# SH4_-_LEVEL_SHIFTERS.net
KiCad netlist of a schematic drawn in Altium Designer
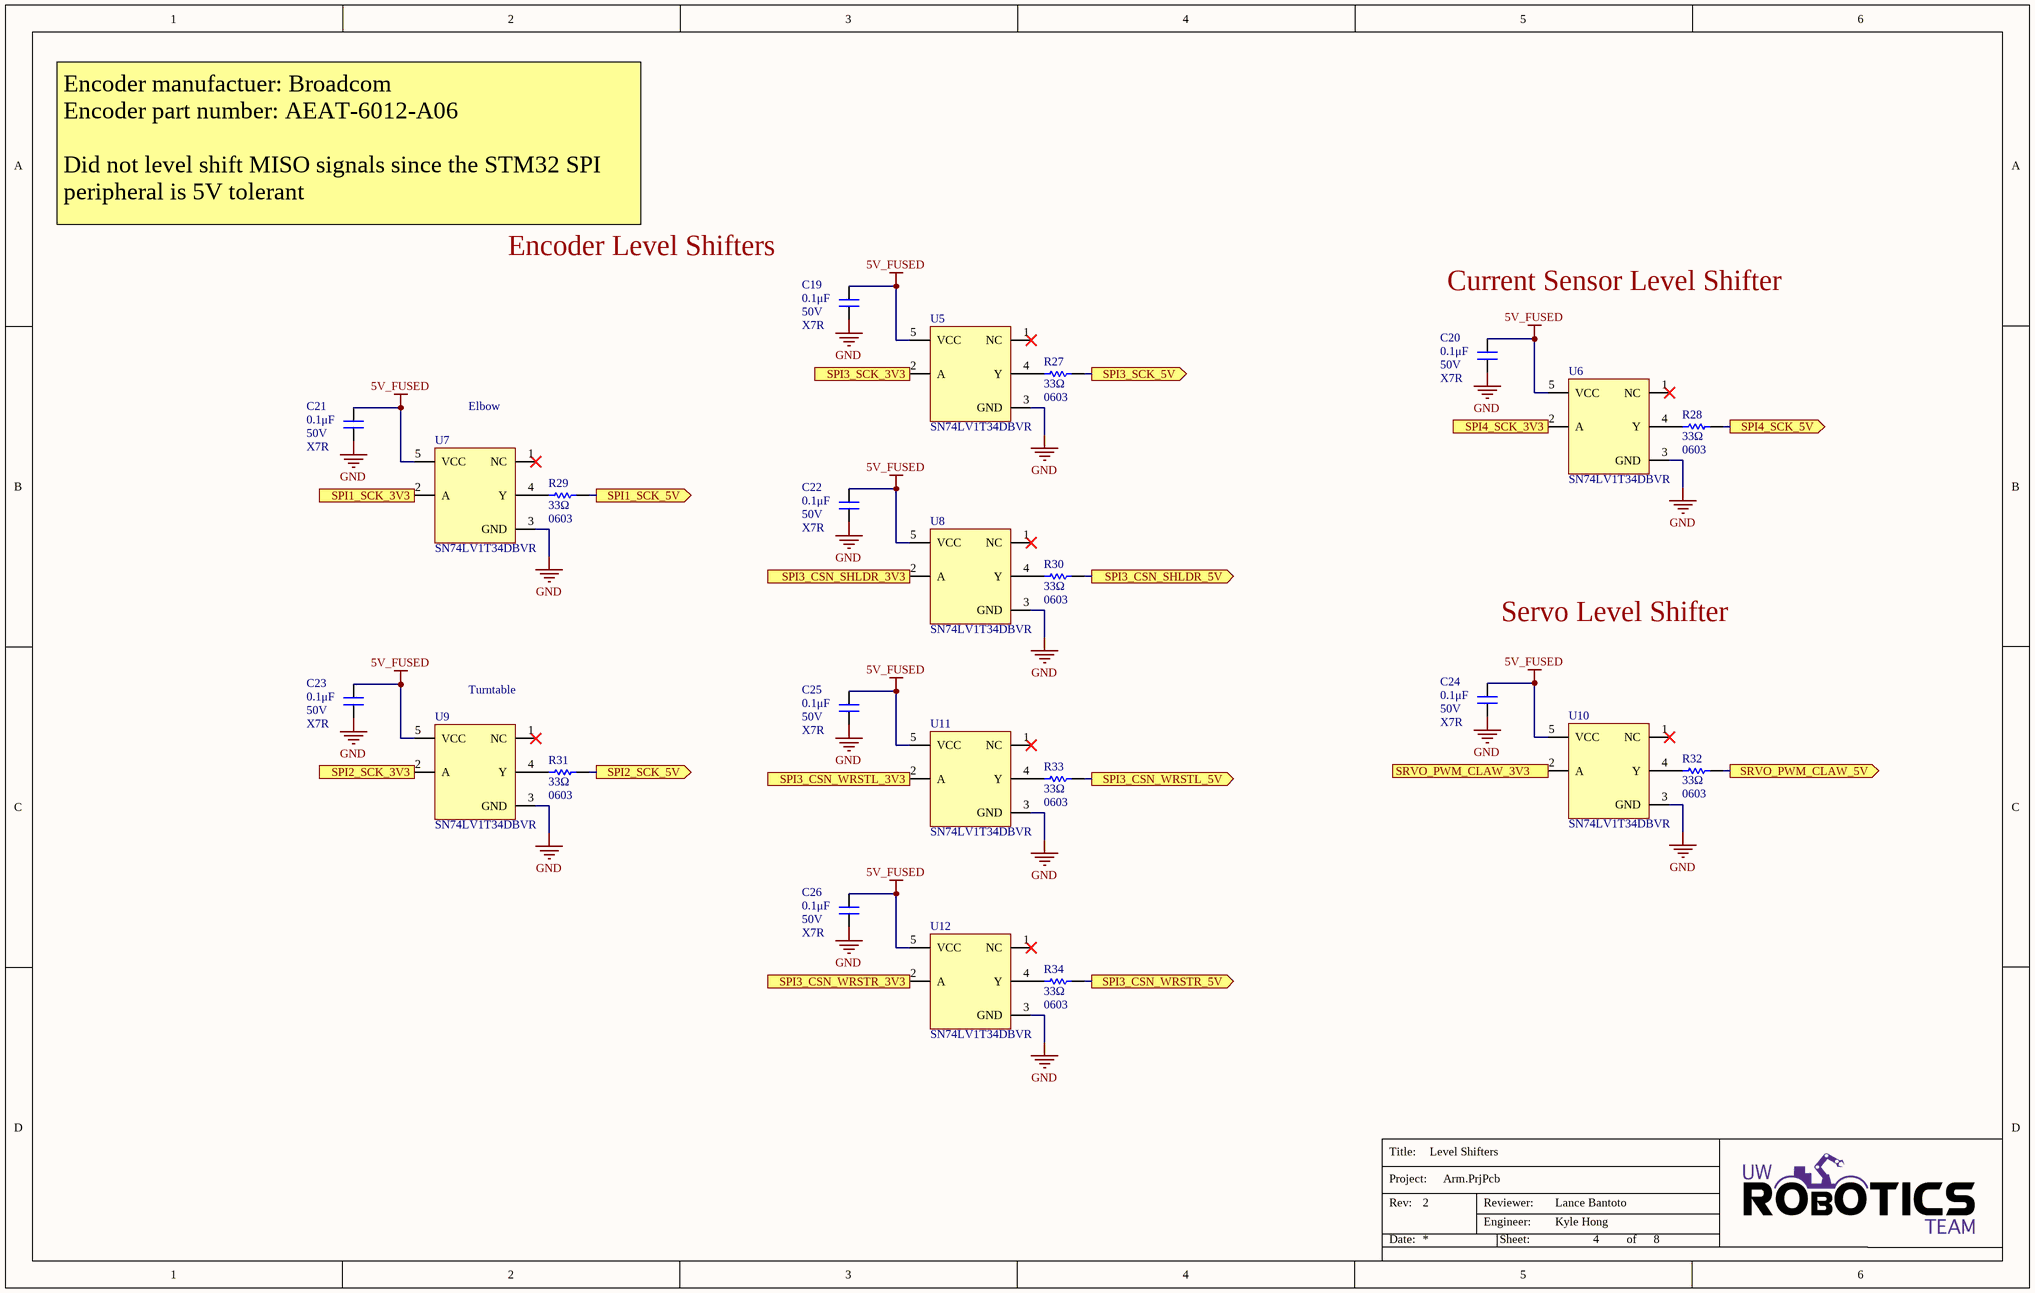
[diagram p0: SH4 - LEVEL SHIFTERS.SchDoc]

(export (version "E")
  (design (tool "Eeschema 10.0.6"))
  (components
    (comp (ref "C19")
      (value "0.1μF")
      (footprint "CAP0603")
      (description "CAP CER 0.1UF 50V X7R 0603")
      (fields
        (field (name "DIELECTRIC") "X7R")
        (field (name "VOLTAGE RATING") "50V")
        (field (name "Comment") "CAP_0.1uF_50V_0603")
      )
      (libsource (lib "UWRT_Schematic_Library_2020") (part "CAP_0.1uF_50V_0603"))
    )
    (comp (ref "C20")
      (value "0.1μF")
      (footprint "CAP0603")
      (description "CAP CER 0.1UF 50V X7R 0603")
      (fields
        (field (name "DIELECTRIC") "X7R")
        (field (name "VOLTAGE RATING") "50V")
        (field (name "Comment") "CAP_0.1uF_50V_0603")
      )
      (libsource (lib "UWRT_Schematic_Library_2020") (part "CAP_0.1uF_50V_0603"))
    )
    (comp (ref "C21")
      (value "0.1μF")
      (footprint "CAP0603")
      (description "CAP CER 0.1UF 50V X7R 0603")
      (fields
        (field (name "DIELECTRIC") "X7R")
        (field (name "VOLTAGE RATING") "50V")
        (field (name "Comment") "CAP_0.1uF_50V_0603")
      )
      (libsource (lib "UWRT_Schematic_Library_2020") (part "CAP_0.1uF_50V_0603"))
    )
    (comp (ref "C22")
      (value "0.1μF")
      (footprint "CAP0603")
      (description "CAP CER 0.1UF 50V X7R 0603")
      (fields
        (field (name "DIELECTRIC") "X7R")
        (field (name "VOLTAGE RATING") "50V")
        (field (name "Comment") "CAP_0.1uF_50V_0603")
      )
      (libsource (lib "UWRT_Schematic_Library_2020") (part "CAP_0.1uF_50V_0603"))
    )
    (comp (ref "C23")
      (value "0.1μF")
      (footprint "CAP0603")
      (description "CAP CER 0.1UF 50V X7R 0603")
      (fields
        (field (name "DIELECTRIC") "X7R")
        (field (name "VOLTAGE RATING") "50V")
        (field (name "Comment") "CAP_0.1uF_50V_0603")
      )
      (libsource (lib "UWRT_Schematic_Library_2020") (part "CAP_0.1uF_50V_0603"))
    )
    (comp (ref "C24")
      (value "0.1μF")
      (footprint "CAP0603")
      (description "CAP CER 0.1UF 50V X7R 0603")
      (fields
        (field (name "DIELECTRIC") "X7R")
        (field (name "VOLTAGE RATING") "50V")
        (field (name "Comment") "CAP_0.1uF_50V_0603")
      )
      (libsource (lib "UWRT_Schematic_Library_2020") (part "CAP_0.1uF_50V_0603"))
    )
    (comp (ref "C25")
      (value "0.1μF")
      (footprint "CAP0603")
      (description "CAP CER 0.1UF 50V X7R 0603")
      (fields
        (field (name "DIELECTRIC") "X7R")
        (field (name "VOLTAGE RATING") "50V")
        (field (name "Comment") "CAP_0.1uF_50V_0603")
      )
      (libsource (lib "UWRT_Schematic_Library_2020") (part "CAP_0.1uF_50V_0603"))
    )
    (comp (ref "C26")
      (value "0.1μF")
      (footprint "CAP0603")
      (description "CAP CER 0.1UF 50V X7R 0603")
      (fields
        (field (name "DIELECTRIC") "X7R")
        (field (name "VOLTAGE RATING") "50V")
        (field (name "Comment") "CAP_0.1uF_50V_0603")
      )
      (libsource (lib "UWRT_Schematic_Library_2020") (part "CAP_0.1uF_50V_0603"))
    )
    (comp (ref "R27")
      (value "RES_33Ω_0603_1%")
      (footprint "RESC0603")
      (description "RES 33 OHM 1% 1/10W 0603")
      (fields
        (field (name "TOLERANCE") "1%")
        (field (name "RESISTANCE") "33Ω")
        (field (name "PACKAGE/FOOTPRINT") "0603")
      )
      (libsource (lib "UWRT_Schematic_Library_2020") (part "RES_33Ω_0603_1%"))
    )
    (comp (ref "R28")
      (value "RES_33Ω_0603_1%")
      (footprint "RESC0603")
      (description "RES 33 OHM 1% 1/10W 0603")
      (fields
        (field (name "TOLERANCE") "1%")
        (field (name "RESISTANCE") "33Ω")
        (field (name "PACKAGE/FOOTPRINT") "0603")
      )
      (libsource (lib "UWRT_Schematic_Library_2020") (part "RES_33Ω_0603_1%"))
    )
    (comp (ref "R29")
      (value "RES_33Ω_0603_1%")
      (footprint "RESC0603")
      (description "RES 33 OHM 1% 1/10W 0603")
      (fields
        (field (name "TOLERANCE") "1%")
        (field (name "RESISTANCE") "33Ω")
        (field (name "PACKAGE/FOOTPRINT") "0603")
      )
      (libsource (lib "UWRT_Schematic_Library_2020") (part "RES_33Ω_0603_1%"))
    )
    (comp (ref "R30")
      (value "RES_33Ω_0603_1%")
      (footprint "RESC0603")
      (description "RES 33 OHM 1% 1/10W 0603")
      (fields
        (field (name "TOLERANCE") "1%")
        (field (name "RESISTANCE") "33Ω")
        (field (name "PACKAGE/FOOTPRINT") "0603")
      )
      (libsource (lib "UWRT_Schematic_Library_2020") (part "RES_33Ω_0603_1%"))
    )
    (comp (ref "R31")
      (value "RES_33Ω_0603_1%")
      (footprint "RESC0603")
      (description "RES 33 OHM 1% 1/10W 0603")
      (fields
        (field (name "TOLERANCE") "1%")
        (field (name "RESISTANCE") "33Ω")
        (field (name "PACKAGE/FOOTPRINT") "0603")
      )
      (libsource (lib "UWRT_Schematic_Library_2020") (part "RES_33Ω_0603_1%"))
    )
    (comp (ref "R32")
      (value "RES_33Ω_0603_1%")
      (footprint "RESC0603")
      (description "RES 33 OHM 1% 1/10W 0603")
      (fields
        (field (name "TOLERANCE") "1%")
        (field (name "RESISTANCE") "33Ω")
        (field (name "PACKAGE/FOOTPRINT") "0603")
      )
      (libsource (lib "UWRT_Schematic_Library_2020") (part "RES_33Ω_0603_1%"))
    )
    (comp (ref "R33")
      (value "RES_33Ω_0603_1%")
      (footprint "RESC0603")
      (description "RES 33 OHM 1% 1/10W 0603")
      (fields
        (field (name "TOLERANCE") "1%")
        (field (name "RESISTANCE") "33Ω")
        (field (name "PACKAGE/FOOTPRINT") "0603")
      )
      (libsource (lib "UWRT_Schematic_Library_2020") (part "RES_33Ω_0603_1%"))
    )
    (comp (ref "R34")
      (value "RES_33Ω_0603_1%")
      (footprint "RESC0603")
      (description "RES 33 OHM 1% 1/10W 0603")
      (fields
        (field (name "TOLERANCE") "1%")
        (field (name "RESISTANCE") "33Ω")
        (field (name "PACKAGE/FOOTPRINT") "0603")
      )
      (libsource (lib "UWRT_Schematic_Library_2020") (part "RES_33Ω_0603_1%"))
    )
    (comp (ref "U5")
      (value "SN74LV1T34")
      (footprint "SN74LV1T34DBVR")
      (description "IC BUF NON-INVERT 5.5V SOT23-5")
      (fields
        (field (name "MANUFACTURER PART NUMBER 1") "SN74LV1T34DBVR")
        (field (name "LCSC PART #") "C100024")
      )
      (libsource (lib "UWRT_Schematic_Library_2020") (part "SN74LV1T34"))
    )
    (comp (ref "U6")
      (value "SN74LV1T34")
      (footprint "SN74LV1T34DBVR")
      (description "IC BUF NON-INVERT 5.5V SOT23-5")
      (fields
        (field (name "MANUFACTURER PART NUMBER 1") "SN74LV1T34DBVR")
        (field (name "LCSC PART #") "C100024")
      )
      (libsource (lib "UWRT_Schematic_Library_2020") (part "SN74LV1T34"))
    )
    (comp (ref "U7")
      (value "SN74LV1T34")
      (footprint "SN74LV1T34DBVR")
      (description "IC BUF NON-INVERT 5.5V SOT23-5")
      (fields
        (field (name "MANUFACTURER PART NUMBER 1") "SN74LV1T34DBVR")
        (field (name "LCSC PART #") "C100024")
      )
      (libsource (lib "UWRT_Schematic_Library_2020") (part "SN74LV1T34"))
    )
    (comp (ref "U8")
      (value "SN74LV1T34")
      (footprint "SN74LV1T34DBVR")
      (description "IC BUF NON-INVERT 5.5V SOT23-5")
      (fields
        (field (name "MANUFACTURER PART NUMBER 1") "SN74LV1T34DBVR")
        (field (name "LCSC PART #") "C100024")
      )
      (libsource (lib "UWRT_Schematic_Library_2020") (part "SN74LV1T34"))
    )
    (comp (ref "U9")
      (value "SN74LV1T34")
      (footprint "SN74LV1T34DBVR")
      (description "IC BUF NON-INVERT 5.5V SOT23-5")
      (fields
        (field (name "MANUFACTURER PART NUMBER 1") "SN74LV1T34DBVR")
        (field (name "LCSC PART #") "C100024")
      )
      (libsource (lib "UWRT_Schematic_Library_2020") (part "SN74LV1T34"))
    )
    (comp (ref "U10")
      (value "SN74LV1T34")
      (footprint "SN74LV1T34DBVR")
      (description "IC BUF NON-INVERT 5.5V SOT23-5")
      (fields
        (field (name "MANUFACTURER PART NUMBER 1") "SN74LV1T34DBVR")
        (field (name "LCSC PART #") "C100024")
      )
      (libsource (lib "UWRT_Schematic_Library_2020") (part "SN74LV1T34"))
    )
    (comp (ref "U11")
      (value "SN74LV1T34")
      (footprint "SN74LV1T34DBVR")
      (description "IC BUF NON-INVERT 5.5V SOT23-5")
      (fields
        (field (name "MANUFACTURER PART NUMBER 1") "SN74LV1T34DBVR")
        (field (name "LCSC PART #") "C100024")
      )
      (libsource (lib "UWRT_Schematic_Library_2020") (part "SN74LV1T34"))
    )
    (comp (ref "U12")
      (value "SN74LV1T34")
      (footprint "SN74LV1T34DBVR")
      (description "IC BUF NON-INVERT 5.5V SOT23-5")
      (fields
        (field (name "MANUFACTURER PART NUMBER 1") "SN74LV1T34DBVR")
        (field (name "LCSC PART #") "C100024")
      )
      (libsource (lib "UWRT_Schematic_Library_2020") (part "SN74LV1T34"))
    )
  )
  (nets
    (net (code "1") (name "/SPI1_SCK_3V3") (class "Default")
      (node (ref "U7") (pin "2") (pinfunction "A_2") (pintype "passive"))
    )
    (net (code "2") (name "/SPI1_SCK_5V") (class "Default")
      (node (ref "R29") (pin "2") (pinfunction "2_2") (pintype "passive"))
    )
    (net (code "3") (name "/SPI2_SCK_3V3") (class "Default")
      (node (ref "U9") (pin "2") (pinfunction "A_2") (pintype "passive"))
    )
    (net (code "4") (name "/SPI2_SCK_5V") (class "Default")
      (node (ref "R31") (pin "2") (pinfunction "2_2") (pintype "passive"))
    )
    (net (code "5") (name "/SPI3_CSN_SHLDR_3V3") (class "Default")
      (node (ref "U8") (pin "2") (pinfunction "A_2") (pintype "passive"))
    )
    (net (code "6") (name "/SPI3_CSN_SHLDR_5V") (class "Default")
      (node (ref "R30") (pin "2") (pinfunction "2_2") (pintype "passive"))
    )
    (net (code "7") (name "/SPI3_CSN_WRSTL_3V3") (class "Default")
      (node (ref "U11") (pin "2") (pinfunction "A_2") (pintype "passive"))
    )
    (net (code "8") (name "/SPI3_CSN_WRSTL_5V") (class "Default")
      (node (ref "R33") (pin "2") (pinfunction "2_2") (pintype "passive"))
    )
    (net (code "9") (name "/SPI3_CSN_WRSTR_3V3") (class "Default")
      (node (ref "U12") (pin "2") (pinfunction "A_2") (pintype "passive"))
    )
    (net (code "10") (name "/SPI3_CSN_WRSTR_5V") (class "Default")
      (node (ref "R34") (pin "2") (pinfunction "2_2") (pintype "passive"))
    )
    (net (code "11") (name "/SPI3_SCK_3V3") (class "Default")
      (node (ref "U5") (pin "2") (pinfunction "A_2") (pintype "passive"))
    )
    (net (code "12") (name "/SPI3_SCK_5V") (class "Default")
      (node (ref "R27") (pin "2") (pinfunction "2_2") (pintype "passive"))
    )
    (net (code "13") (name "/SPI4_SCK_3V3") (class "Default")
      (node (ref "U6") (pin "2") (pinfunction "A_2") (pintype "passive"))
    )
    (net (code "14") (name "/SPI4_SCK_5V") (class "Default")
      (node (ref "R28") (pin "2") (pinfunction "2_2") (pintype "passive"))
    )
    (net (code "15") (name "/SRVO_PWM_CLAW_3V3") (class "Default")
      (node (ref "U10") (pin "2") (pinfunction "A_2") (pintype "passive"))
    )
    (net (code "16") (name "/SRVO_PWM_CLAW_5V") (class "Default")
      (node (ref "R32") (pin "2") (pinfunction "2_2") (pintype "passive"))
    )
    (net (code "17") (name "5V_FUSED") (class "Default")
      (node (ref "C19") (pin "2") (pinfunction "2_2") (pintype "passive"))
      (node (ref "C20") (pin "2") (pinfunction "2_2") (pintype "passive"))
      (node (ref "C21") (pin "2") (pinfunction "2_2") (pintype "passive"))
      (node (ref "C22") (pin "2") (pinfunction "2_2") (pintype "passive"))
      (node (ref "C23") (pin "2") (pinfunction "2_2") (pintype "passive"))
      (node (ref "C24") (pin "2") (pinfunction "2_2") (pintype "passive"))
      (node (ref "C25") (pin "2") (pinfunction "2_2") (pintype "passive"))
      (node (ref "C26") (pin "2") (pinfunction "2_2") (pintype "passive"))
      (node (ref "U10") (pin "5") (pinfunction "VCC_5") (pintype "passive"))
      (node (ref "U11") (pin "5") (pinfunction "VCC_5") (pintype "passive"))
      (node (ref "U12") (pin "5") (pinfunction "VCC_5") (pintype "passive"))
      (node (ref "U5") (pin "5") (pinfunction "VCC_5") (pintype "passive"))
      (node (ref "U6") (pin "5") (pinfunction "VCC_5") (pintype "passive"))
      (node (ref "U7") (pin "5") (pinfunction "VCC_5") (pintype "passive"))
      (node (ref "U8") (pin "5") (pinfunction "VCC_5") (pintype "passive"))
      (node (ref "U9") (pin "5") (pinfunction "VCC_5") (pintype "passive"))
    )
    (net (code "18") (name "GND") (class "Default")
      (node (ref "C19") (pin "1") (pinfunction "1_1") (pintype "passive"))
      (node (ref "C20") (pin "1") (pinfunction "1_1") (pintype "passive"))
      (node (ref "C21") (pin "1") (pinfunction "1_1") (pintype "passive"))
      (node (ref "C22") (pin "1") (pinfunction "1_1") (pintype "passive"))
      (node (ref "C23") (pin "1") (pinfunction "1_1") (pintype "passive"))
      (node (ref "C24") (pin "1") (pinfunction "1_1") (pintype "passive"))
      (node (ref "C25") (pin "1") (pinfunction "1_1") (pintype "passive"))
      (node (ref "C26") (pin "1") (pinfunction "1_1") (pintype "passive"))
      (node (ref "U10") (pin "3") (pinfunction "GND_3") (pintype "passive"))
      (node (ref "U11") (pin "3") (pinfunction "GND_3") (pintype "passive"))
      (node (ref "U12") (pin "3") (pinfunction "GND_3") (pintype "passive"))
      (node (ref "U5") (pin "3") (pinfunction "GND_3") (pintype "passive"))
      (node (ref "U6") (pin "3") (pinfunction "GND_3") (pintype "passive"))
      (node (ref "U7") (pin "3") (pinfunction "GND_3") (pintype "passive"))
      (node (ref "U8") (pin "3") (pinfunction "GND_3") (pintype "passive"))
      (node (ref "U9") (pin "3") (pinfunction "GND_3") (pintype "passive"))
    )
    (net (code "19") (name "Net-(U5-Y)") (class "Default")
      (node (ref "R27") (pin "1") (pinfunction "1_1") (pintype "passive"))
      (node (ref "U5") (pin "4") (pinfunction "Y_4") (pintype "passive"))
    )
    (net (code "20") (name "Net-(U6-Y)") (class "Default")
      (node (ref "R28") (pin "1") (pinfunction "1_1") (pintype "passive"))
      (node (ref "U6") (pin "4") (pinfunction "Y_4") (pintype "passive"))
    )
    (net (code "21") (name "Net-(U7-Y)") (class "Default")
      (node (ref "R29") (pin "1") (pinfunction "1_1") (pintype "passive"))
      (node (ref "U7") (pin "4") (pinfunction "Y_4") (pintype "passive"))
    )
    (net (code "22") (name "Net-(U8-Y)") (class "Default")
      (node (ref "R30") (pin "1") (pinfunction "1_1") (pintype "passive"))
      (node (ref "U8") (pin "4") (pinfunction "Y_4") (pintype "passive"))
    )
    (net (code "23") (name "Net-(U9-Y)") (class "Default")
      (node (ref "R31") (pin "1") (pinfunction "1_1") (pintype "passive"))
      (node (ref "U9") (pin "4") (pinfunction "Y_4") (pintype "passive"))
    )
    (net (code "24") (name "Net-(U10-Y)") (class "Default")
      (node (ref "R32") (pin "1") (pinfunction "1_1") (pintype "passive"))
      (node (ref "U10") (pin "4") (pinfunction "Y_4") (pintype "passive"))
    )
    (net (code "25") (name "Net-(U11-Y)") (class "Default")
      (node (ref "R33") (pin "1") (pinfunction "1_1") (pintype "passive"))
      (node (ref "U11") (pin "4") (pinfunction "Y_4") (pintype "passive"))
    )
    (net (code "26") (name "Net-(U12-Y)") (class "Default")
      (node (ref "R34") (pin "1") (pinfunction "1_1") (pintype "passive"))
      (node (ref "U12") (pin "4") (pinfunction "Y_4") (pintype "passive"))
    )
    (net (code "27") (name "unconnected-(U5-NC-Pad1)") (class "Default")
      (node (ref "U5") (pin "1") (pinfunction "NC_1") (pintype "passive+no_connect"))
    )
    (net (code "28") (name "unconnected-(U6-NC-Pad1)") (class "Default")
      (node (ref "U6") (pin "1") (pinfunction "NC_1") (pintype "passive+no_connect"))
    )
    (net (code "29") (name "unconnected-(U7-NC-Pad1)") (class "Default")
      (node (ref "U7") (pin "1") (pinfunction "NC_1") (pintype "passive+no_connect"))
    )
    (net (code "30") (name "unconnected-(U8-NC-Pad1)") (class "Default")
      (node (ref "U8") (pin "1") (pinfunction "NC_1") (pintype "passive+no_connect"))
    )
    (net (code "31") (name "unconnected-(U9-NC-Pad1)") (class "Default")
      (node (ref "U9") (pin "1") (pinfunction "NC_1") (pintype "passive+no_connect"))
    )
    (net (code "32") (name "unconnected-(U10-NC-Pad1)") (class "Default")
      (node (ref "U10") (pin "1") (pinfunction "NC_1") (pintype "passive+no_connect"))
    )
    (net (code "33") (name "unconnected-(U11-NC-Pad1)") (class "Default")
      (node (ref "U11") (pin "1") (pinfunction "NC_1") (pintype "passive+no_connect"))
    )
    (net (code "34") (name "unconnected-(U12-NC-Pad1)") (class "Default")
      (node (ref "U12") (pin "1") (pinfunction "NC_1") (pintype "passive+no_connect"))
    )
  )
)
